# BAR30-SENSOR.net
KiCad netlist of a schematic drawn in EAGLE
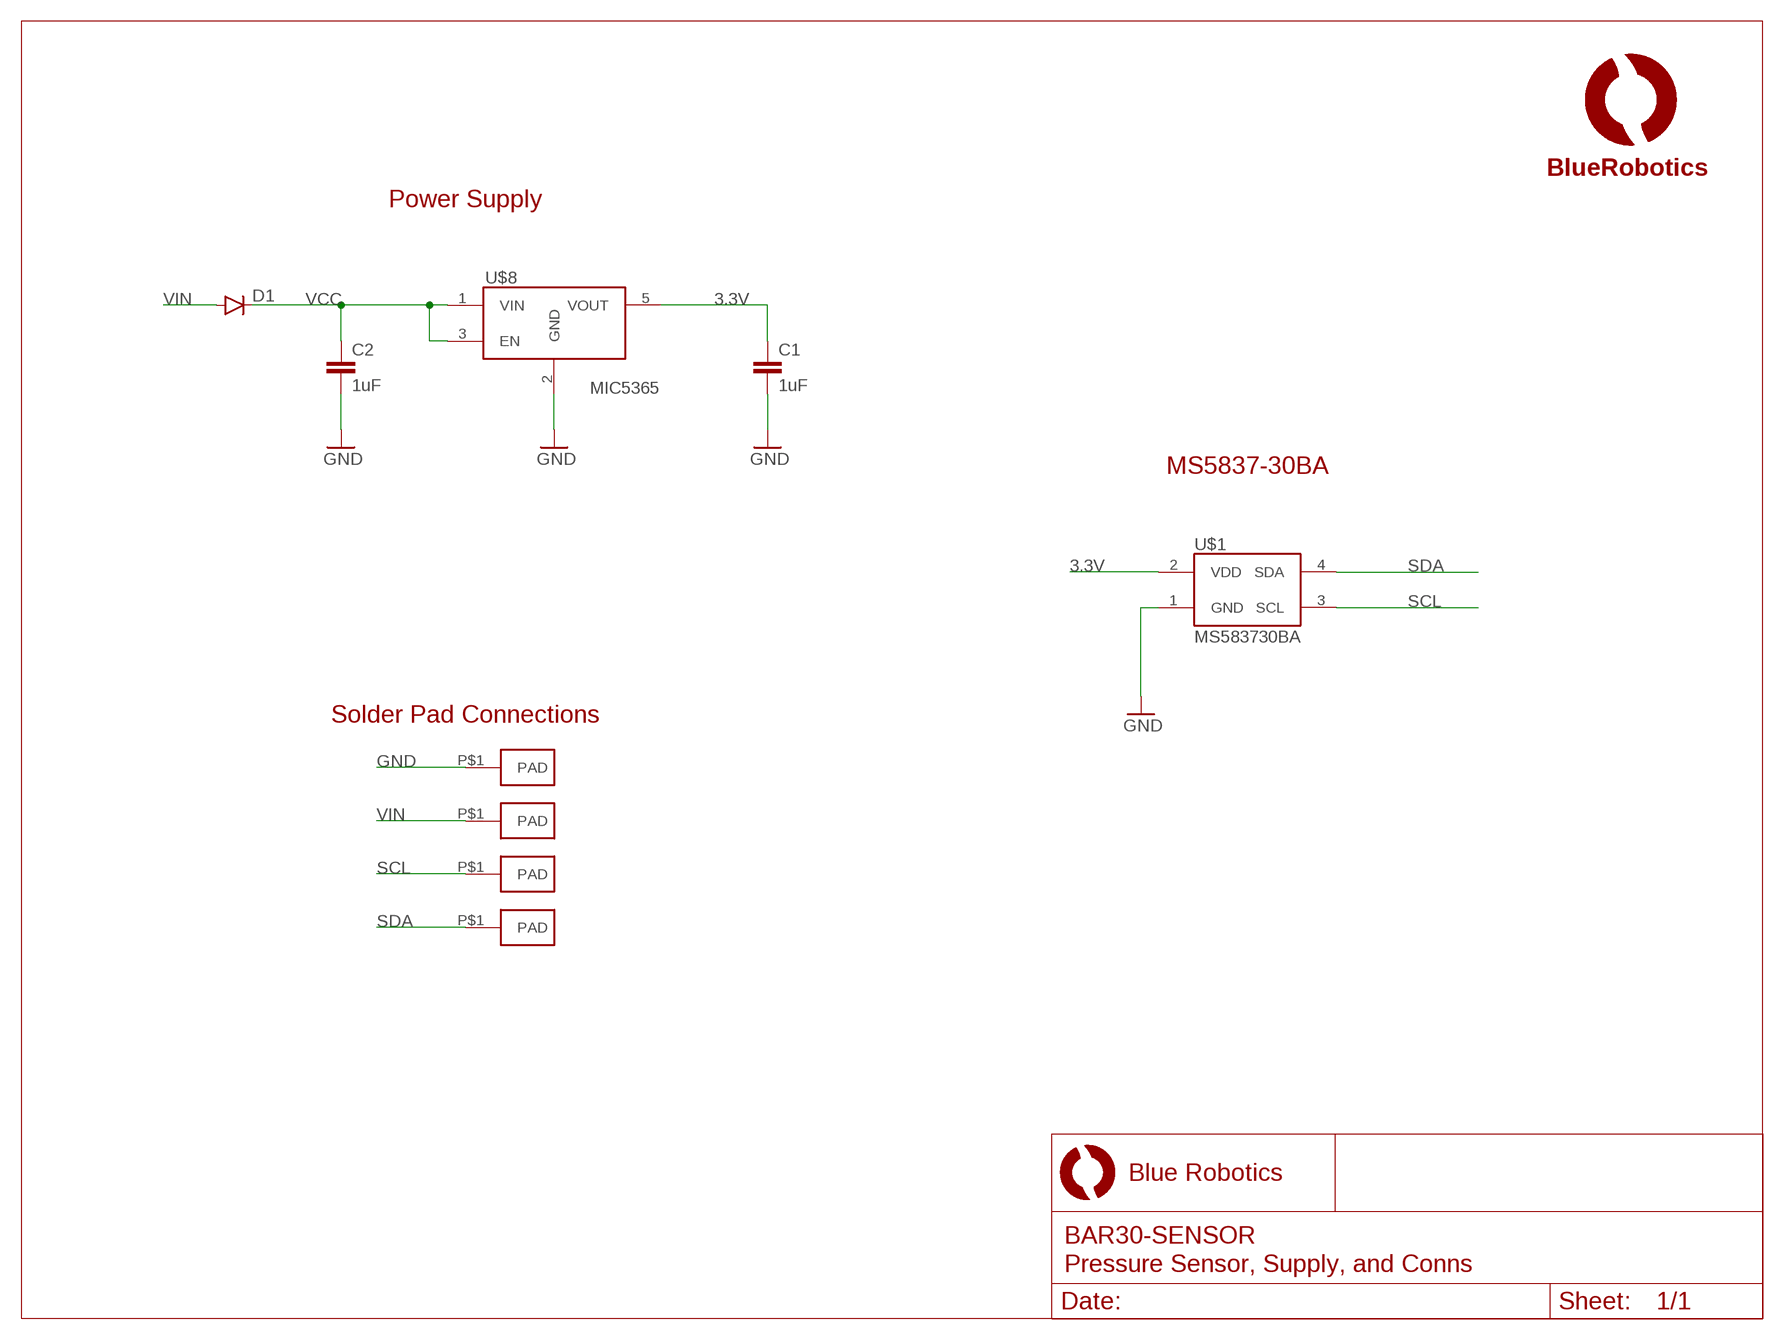
[diagram p0: schematic, sheet 1]

(export (version "E")
  (design (tool "Eeschema 10.0.6"))
  (components
    (comp (ref "C1")
      (value "1uF")
      (footprint "eagle-import:C0402")
      (libsource (lib "eagle-import") (part "C-EUC0402"))
    )
    (comp (ref "C2")
      (value "1uF")
      (footprint "eagle-import:C0402")
      (libsource (lib "eagle-import") (part "C-EUC0402"))
    )
    (comp (ref "D1")
      (value "DIODESOD523")
      (footprint "eagle-import:SOD523")
      (libsource (lib "eagle-import") (part "DIODESOD523"))
    )
    (comp (ref "U$1")
      (value "MS583730BA")
      (footprint "eagle-import:MS5837")
      (libsource (lib "eagle-import") (part "MS583730BA"))
    )
    (comp (ref "U$3")
      (value "PAD1.5X3MM")
      (footprint "eagle-import:PAD-1.5X3MM")
      (libsource (lib "eagle-import") (part "PAD1.5X3MM"))
    )
    (comp (ref "U$4")
      (value "PAD1.5X3MM")
      (footprint "eagle-import:PAD-1.5X3MM")
      (libsource (lib "eagle-import") (part "PAD1.5X3MM"))
    )
    (comp (ref "U$5")
      (value "PAD1.5X3MM")
      (footprint "eagle-import:PAD-1.5X3MM")
      (libsource (lib "eagle-import") (part "PAD1.5X3MM"))
    )
    (comp (ref "U$6")
      (value "PAD1.5X3MM")
      (footprint "eagle-import:PAD-1.5X3MM")
      (libsource (lib "eagle-import") (part "PAD1.5X3MM"))
    )
    (comp (ref "U$7")
      (value "LOGOBR-LOGO-S")
      (footprint "eagle-import:BR-LOGO-SMALL")
      (libsource (lib "eagle-import") (part "LOGOBR-LOGO-S"))
    )
    (comp (ref "U$8")
      (value "VREG-MIC5365")
      (footprint "eagle-import:SC70-5L")
      (libsource (lib "eagle-import") (part "VREG-MIC5365"))
    )
  )
  (nets
    (net (code "1") (name "/3.3V") (class "Default")
      (node (ref "C1") (pin "1") (pinfunction "1_1") (pintype "passive"))
      (node (ref "U$1") (pin "2") (pinfunction "VDD_2") (pintype "bidirectional"))
      (node (ref "U$8") (pin "5") (pinfunction "VOUT_5") (pintype "bidirectional"))
    )
    (net (code "2") (name "/SCL") (class "Default")
      (node (ref "U$1") (pin "3") (pinfunction "SCL_3") (pintype "bidirectional"))
      (node (ref "U$5") (pin "P$1") (pinfunction "PAD_P$1") (pintype "bidirectional"))
    )
    (net (code "3") (name "/SDA") (class "Default")
      (node (ref "U$1") (pin "4") (pinfunction "SDA_4") (pintype "bidirectional"))
      (node (ref "U$6") (pin "P$1") (pinfunction "PAD_P$1") (pintype "bidirectional"))
    )
    (net (code "4") (name "/VCC") (class "Default")
      (node (ref "C2") (pin "1") (pinfunction "1_1") (pintype "passive"))
      (node (ref "D1") (pin "C") (pinfunction "C_C") (pintype "passive"))
      (node (ref "U$8") (pin "1") (pinfunction "VIN_1") (pintype "bidirectional"))
      (node (ref "U$8") (pin "3") (pinfunction "EN_3") (pintype "bidirectional"))
    )
    (net (code "5") (name "/VIN") (class "Default")
      (node (ref "D1") (pin "A") (pinfunction "A_A") (pintype "passive"))
      (node (ref "U$4") (pin "P$1") (pinfunction "PAD_P$1") (pintype "bidirectional"))
    )
    (net (code "6") (name "GND") (class "Default")
      (node (ref "C1") (pin "2") (pinfunction "2_2") (pintype "passive"))
      (node (ref "C2") (pin "2") (pinfunction "2_2") (pintype "passive"))
      (node (ref "U$1") (pin "1") (pinfunction "GND_1") (pintype "bidirectional"))
      (node (ref "U$3") (pin "P$1") (pinfunction "PAD_P$1") (pintype "bidirectional"))
      (node (ref "U$8") (pin "2") (pinfunction "GND_2") (pintype "bidirectional"))
    )
  )
)
